# 18500_pack_v1.net
KiCad netlist of a schematic drawn in EAGLE
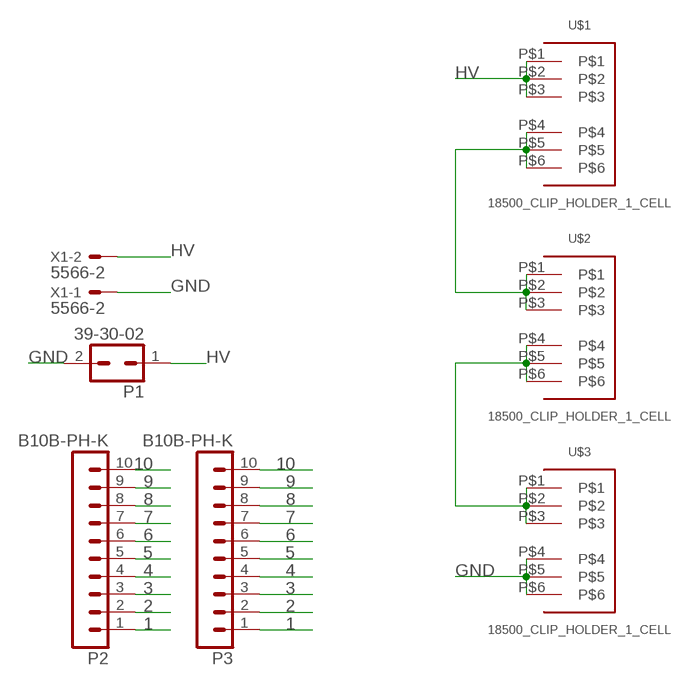
[diagram p0: schematic, sheet 1]

(export (version "E")
  (design (tool "Eeschema 10.0.6"))
  (components
    (comp (ref "P1")
      (value "39-30-02")
      (footprint "eagle-import:39-30-_02_")
      (libsource (lib "eagle-import") (part "39-30-?02?"))
    )
    (comp (ref "P2")
      (value "B10B-PH-K")
      (footprint "eagle-import:B10B-PH-K")
      (libsource (lib "eagle-import") (part "B10B-PH-K"))
    )
    (comp (ref "P3")
      (value "B10B-PH-K")
      (footprint "eagle-import:B10B-PH-K")
      (libsource (lib "eagle-import") (part "B10B-PH-K"))
    )
    (comp (ref "U$1")
      (value "18500_CLIP_HOLDER_1_CELL")
      (footprint "eagle-import:3PINBATTERY_CLIP_1_CELL_18500")
      (libsource (lib "eagle-import") (part "18500_CLIP_HOLDER_1_CELL"))
    )
    (comp (ref "U$2")
      (value "18500_CLIP_HOLDER_1_CELL")
      (footprint "eagle-import:3PINBATTERY_CLIP_1_CELL_18500")
      (libsource (lib "eagle-import") (part "18500_CLIP_HOLDER_1_CELL"))
    )
    (comp (ref "U$3")
      (value "18500_CLIP_HOLDER_1_CELL")
      (footprint "eagle-import:3PINBATTERY_CLIP_1_CELL_18500")
      (libsource (lib "eagle-import") (part "18500_CLIP_HOLDER_1_CELL"))
    )
    (comp (ref "X1")
      (value "5566-2")
      (footprint "eagle-import:5566-2")
      (fields (field (name "MF") "MOLEX"))
      (libsource (lib "eagle-import") (part "5566-2"))
    )
  )
  (nets
    (net (code "1") (name "/1") (class "Default")
      (node (ref "P2") (pin "1") (pinfunction "1_1") (pintype "passive"))
      (node (ref "P3") (pin "1") (pinfunction "1_1") (pintype "passive"))
    )
    (net (code "2") (name "/2") (class "Default")
      (node (ref "P2") (pin "2") (pinfunction "2_2") (pintype "passive"))
      (node (ref "P3") (pin "2") (pinfunction "2_2") (pintype "passive"))
    )
    (net (code "3") (name "/3") (class "Default")
      (node (ref "P2") (pin "3") (pinfunction "3_3") (pintype "passive"))
      (node (ref "P3") (pin "3") (pinfunction "3_3") (pintype "passive"))
    )
    (net (code "4") (name "/4") (class "Default")
      (node (ref "P2") (pin "4") (pinfunction "4_4") (pintype "passive"))
      (node (ref "P3") (pin "4") (pinfunction "4_4") (pintype "passive"))
    )
    (net (code "5") (name "/5") (class "Default")
      (node (ref "P2") (pin "5") (pinfunction "5_5") (pintype "passive"))
      (node (ref "P3") (pin "5") (pinfunction "5_5") (pintype "passive"))
    )
    (net (code "6") (name "/6") (class "Default")
      (node (ref "P2") (pin "6") (pinfunction "6_6") (pintype "passive"))
      (node (ref "P3") (pin "6") (pinfunction "6_6") (pintype "passive"))
    )
    (net (code "7") (name "/7") (class "Default")
      (node (ref "P2") (pin "7") (pinfunction "7_7") (pintype "passive"))
      (node (ref "P3") (pin "7") (pinfunction "7_7") (pintype "passive"))
    )
    (net (code "8") (name "/8") (class "Default")
      (node (ref "P2") (pin "8") (pinfunction "8_8") (pintype "passive"))
      (node (ref "P3") (pin "8") (pinfunction "8_8") (pintype "passive"))
    )
    (net (code "9") (name "/9") (class "Default")
      (node (ref "P2") (pin "9") (pinfunction "9_9") (pintype "passive"))
      (node (ref "P3") (pin "9") (pinfunction "9_9") (pintype "passive"))
    )
    (net (code "10") (name "/10") (class "Default")
      (node (ref "P2") (pin "10") (pinfunction "10_10") (pintype "passive"))
      (node (ref "P3") (pin "10") (pinfunction "10_10") (pintype "passive"))
    )
    (net (code "11") (name "/GND") (class "Default")
      (node (ref "P1") (pin "2") (pinfunction "2_2") (pintype "passive"))
      (node (ref "U$3") (pin "P$4") (pinfunction "P$4_P$4") (pintype "bidirectional"))
      (node (ref "U$3") (pin "P$5") (pinfunction "P$5_P$5") (pintype "bidirectional"))
      (node (ref "U$3") (pin "P$6") (pinfunction "P$6_P$6") (pintype "bidirectional"))
      (node (ref "X1") (pin "1") (pinfunction "S_1") (pintype "passive"))
    )
    (net (code "12") (name "/HV") (class "Default")
      (node (ref "P1") (pin "1") (pinfunction "1_1") (pintype "passive"))
      (node (ref "U$1") (pin "P$1") (pinfunction "P$1_P$1") (pintype "bidirectional"))
      (node (ref "U$1") (pin "P$2") (pinfunction "P$2_P$2") (pintype "bidirectional"))
      (node (ref "U$1") (pin "P$3") (pinfunction "P$3_P$3") (pintype "bidirectional"))
      (node (ref "X1") (pin "2") (pinfunction "S_2") (pintype "passive"))
    )
    (net (code "13") (name "Net-(U$1-PadP$4)") (class "Default")
      (node (ref "U$1") (pin "P$4") (pinfunction "P$4_P$4") (pintype "bidirectional"))
      (node (ref "U$1") (pin "P$5") (pinfunction "P$5_P$5") (pintype "bidirectional"))
      (node (ref "U$1") (pin "P$6") (pinfunction "P$6_P$6") (pintype "bidirectional"))
      (node (ref "U$2") (pin "P$1") (pinfunction "P$1_P$1") (pintype "bidirectional"))
      (node (ref "U$2") (pin "P$2") (pinfunction "P$2_P$2") (pintype "bidirectional"))
      (node (ref "U$2") (pin "P$3") (pinfunction "P$3_P$3") (pintype "bidirectional"))
    )
    (net (code "14") (name "Net-(U$2-PadP$4)") (class "Default")
      (node (ref "U$2") (pin "P$4") (pinfunction "P$4_P$4") (pintype "bidirectional"))
      (node (ref "U$2") (pin "P$5") (pinfunction "P$5_P$5") (pintype "bidirectional"))
      (node (ref "U$2") (pin "P$6") (pinfunction "P$6_P$6") (pintype "bidirectional"))
      (node (ref "U$3") (pin "P$1") (pinfunction "P$1_P$1") (pintype "bidirectional"))
      (node (ref "U$3") (pin "P$2") (pinfunction "P$2_P$2") (pintype "bidirectional"))
      (node (ref "U$3") (pin "P$3") (pinfunction "P$3_P$3") (pintype "bidirectional"))
    )
  )
)
